# HIVE_SIGHT_WROOM.net
KiCad netlist of a schematic drawn in Altium Designer
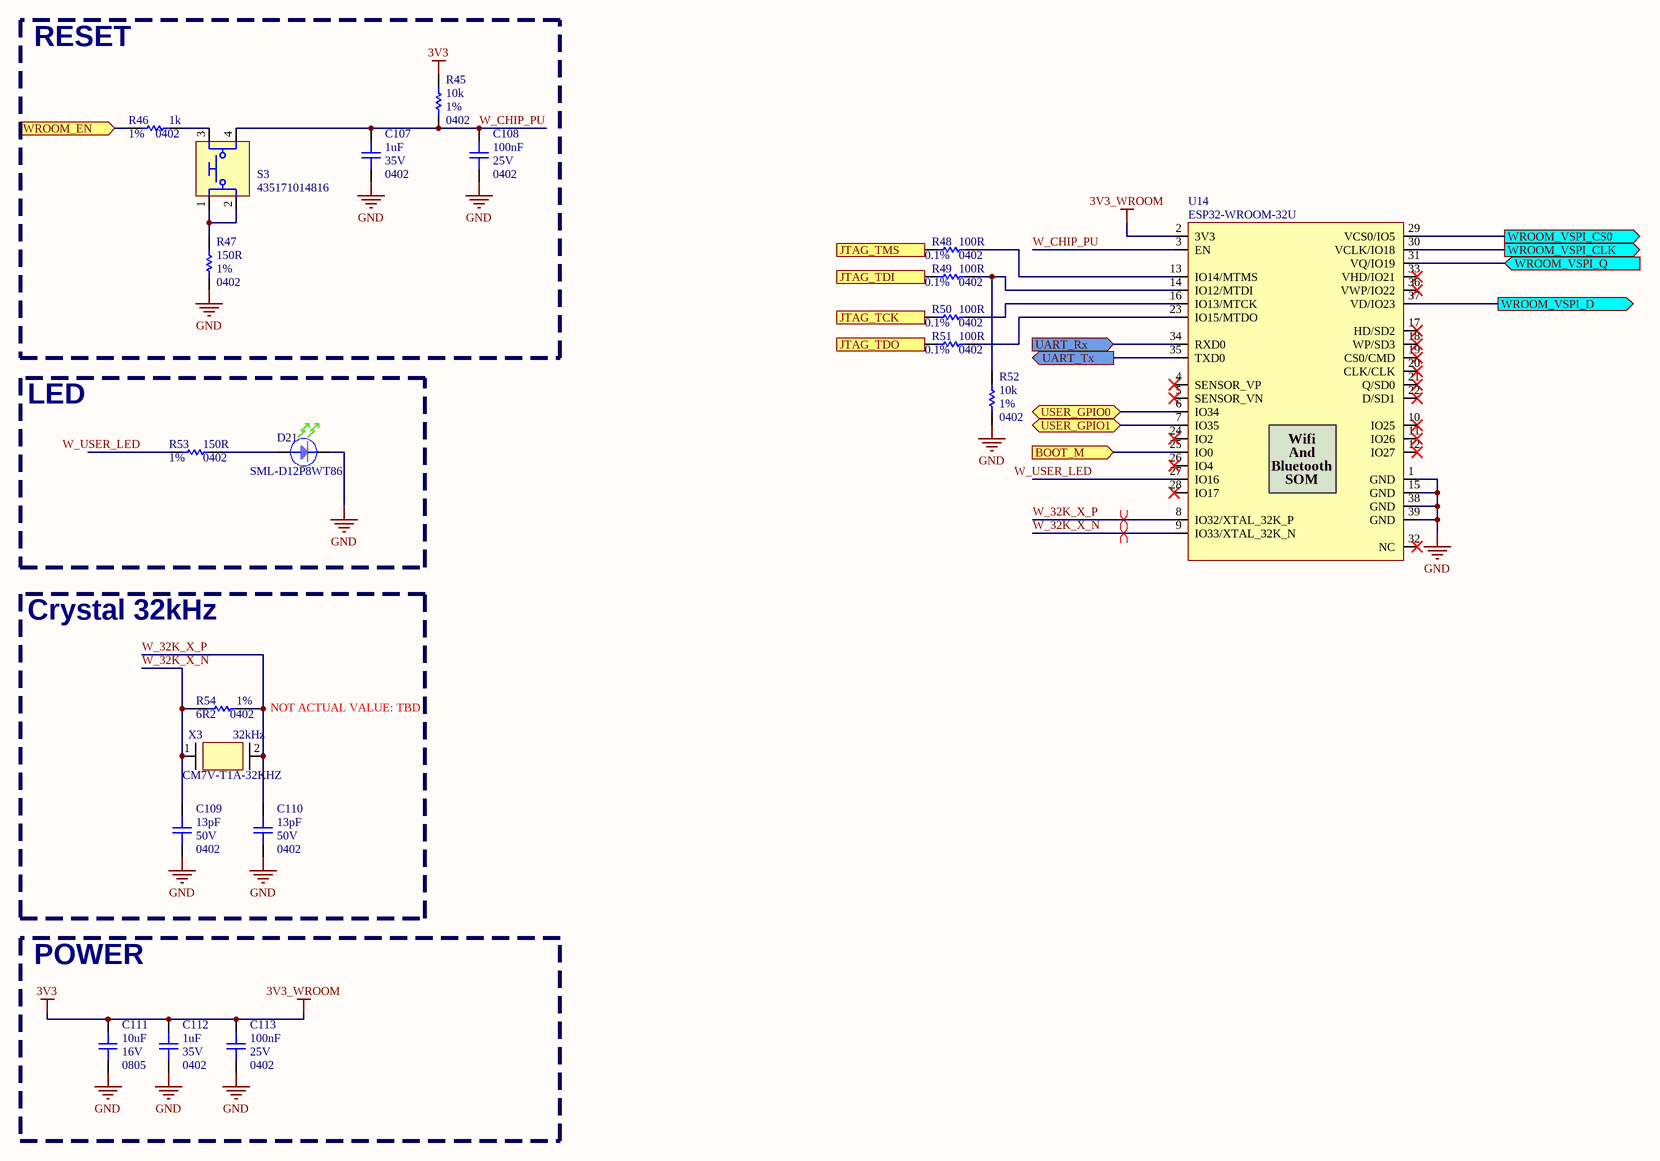
[diagram p0: HIVE_SIGHT_WROOM.SchDoc]

(export (version "E")
  (design (tool "Eeschema 10.0.6"))
  (components
    (comp (ref "C107")
      (value "1uF")
      (footprint "GRAMS_MASTER_LIB_PCB:CAP_CER_0402")
      (description "CAP - CER 1uF 10% 35V X5R - 0402")
      (fields
        (field (name "TOLERANCE") "10%")
        (field (name "PACKAGE") "0402")
        (field (name "VOLTAGE RATING") "35V")
        (field (name "Comment") "CL05A105KL5NRNC")
        (field (name "CREATEDBY/DATE") "Nicolas Roy 2018-10-03")
        (field (name "VERIFIEDBY") "Caroline Paulin - 18 janv 2019")
      )
      (libsource (lib "GRAMS_MASTER_LIB_SCH") (part "CAP_CER_CL05A105KL5NRNC"))
    )
    (comp (ref "C108")
      (value "100nF")
      (footprint "GRAMS_MASTER_LIB_PCB:CAP_CER_0402")
      (description "CAP - CER 0.1µF 10% 25V X7R - 0402")
      (fields
        (field (name "TOLERANCE") "10%")
        (field (name "PACKAGE") "0402")
        (field (name "VOLTAGE RATING") "25V")
        (field (name "Comment") "CGA2B3X7R1E104K050BB")
        (field (name "CREATEDBY/DATE") "Nicolas Roy 2018-11-07")
        (field (name "VERIFIEDBY") "Nicolas V. (2019-01-22)")
      )
      (libsource (lib "GRAMS_MASTER_LIB_SCH") (part "CAP_CER_CGA2B3X7R1E104K050BB"))
    )
    (comp (ref "C109")
      (value "13pF")
      (footprint "CAP_CER_0402")
      (description "CAP - CER 13PF 50V C0G/NP0 - 0402")
      (fields
        (field (name "TOLERANCE") "±5%")
        (field (name "PACKAGE") "0402")
        (field (name "VOLTAGE RATING") "50V")
        (field (name "Comment") "CC0402JRNPO9BN130")
        (field (name "CREATEDBY/DATE") "Hubert Dube - 04/10/20")
        (field (name "VERIFIEDBY") "Louis-Daniel Gaulin - 09/11/2020")
      )
      (libsource (lib "SWARMUS_LIB") (part "CAP_CER_CC0402JRNPO9BN130"))
    )
    (comp (ref "C110")
      (value "13pF")
      (footprint "CAP_CER_0402")
      (description "CAP - CER 13PF 50V C0G/NP0 - 0402")
      (fields
        (field (name "TOLERANCE") "±5%")
        (field (name "PACKAGE") "0402")
        (field (name "VOLTAGE RATING") "50V")
        (field (name "Comment") "CC0402JRNPO9BN130")
        (field (name "CREATEDBY/DATE") "Hubert Dube - 04/10/20")
        (field (name "VERIFIEDBY") "Louis-Daniel Gaulin - 09/11/2020")
      )
      (libsource (lib "SWARMUS_LIB") (part "CAP_CER_CC0402JRNPO9BN130"))
    )
    (comp (ref "C111")
      (value "10uF")
      (footprint "CAP_CER_0805")
      (description "CAP - CER 10UF 10% 16V X5R - 0805")
      (fields
        (field (name "TOLERANCE") "10%")
        (field (name "PACKAGE") "0805")
        (field (name "VOLTAGE RATING") "16V")
        (field (name "Comment") "GRM21BR61C106KE15K")
        (field (name "CREATEDBY/DATE") "Caroline Paulin / 8 août 2018")
        (field (name "VERIFIEDBY") "Nicolas V. (2019-01-22)")
      )
      (libsource (lib "GRAMS_MASTER_LIB") (part "CAP_CER_GRM21BR61C106KE15K"))
    )
    (comp (ref "C112")
      (value "1uF")
      (footprint "GRAMS_MASTER_LIB_PCB:CAP_CER_0402")
      (description "CAP - CER 1uF 10% 35V X5R - 0402")
      (fields
        (field (name "TOLERANCE") "10%")
        (field (name "PACKAGE") "0402")
        (field (name "VOLTAGE RATING") "35V")
        (field (name "Comment") "CL05A105KL5NRNC")
        (field (name "CREATEDBY/DATE") "Nicolas Roy 2018-10-03")
        (field (name "VERIFIEDBY") "Caroline Paulin - 18 janv 2019")
      )
      (libsource (lib "GRAMS_MASTER_LIB_SCH") (part "CAP_CER_CL05A105KL5NRNC"))
    )
    (comp (ref "C113")
      (value "100nF")
      (footprint "GRAMS_MASTER_LIB_PCB:CAP_CER_0402")
      (description "CAP - CER 0.1µF 10% 25V X7R - 0402")
      (fields
        (field (name "TOLERANCE") "10%")
        (field (name "PACKAGE") "0402")
        (field (name "VOLTAGE RATING") "25V")
        (field (name "Comment") "CGA2B3X7R1E104K050BB")
        (field (name "CREATEDBY/DATE") "Nicolas Roy 2018-11-07")
        (field (name "VERIFIEDBY") "Nicolas V. (2019-01-22)")
      )
      (libsource (lib "GRAMS_MASTER_LIB_SCH") (part "CAP_CER_CGA2B3X7R1E104K050BB"))
    )
    (comp (ref "D21")
      (value "SML-D12P8WT86")
      (footprint "GRAMS_MASTER_LIB_PCB:LED_SML-D12P8WT86")
      (description "LED - GREEN DIFFUSED 0603 SMD - 0603")
      (fields
        (field (name "CREATEDBY/DATE") "Keven Deslandes - 2018/11/21")
        (field (name "VERIFIEDBY") "Caroline Paulin - 13 février 2019")
      )
      (libsource (lib "GRAMS_MASTER_LIB_SCH") (part "LED_SML-D12P8WT86"))
    )
    (comp (ref "R45")
      (value "10k")
      (footprint "GRAMS_MASTER_LIB_PCB:RES_0402")
      (description "RES - 10K OHMS 1% 1/16W - 0402")
      (fields
        (field (name "TOLERANCE") "1%")
        (field (name "PACKAGE") "0402")
        (field (name "Comment") "RC0402FR-0710KL")
        (field (name "CREATEDBY/DATE") "Nicolas V. (2018-11-20)")
        (field (name "VERIFIEDBY") "Nicolas V. (2018-11-20)")
      )
      (libsource (lib "GRAMS_MASTER_LIB_SCH") (part "RES_RC0402FR-0710KL"))
    )
    (comp (ref "R46")
      (value "1k")
      (footprint "GRAMS_MASTER_LIB_PCB:RES_0402")
      (description "RES - 1K OHM 1% 1/16W - 0402")
      (fields
        (field (name "TOLERANCE") "1%")
        (field (name "PACKAGE") "0402")
        (field (name "Comment") "RC0402FR-071KL")
        (field (name "CREATEDBY/DATE") "Jonathan Bouchard 2018-07-05")
        (field (name "VERIFIEDBY") "Arnaud Samson 16-07-18")
      )
      (libsource (lib "GRAMS_MASTER_LIB_SCH") (part "RES_RC0402FR-071KL"))
    )
    (comp (ref "R47")
      (value "150R")
      (footprint "RES_0402")
      (description "RES - 150R 1% 1/16W - 0402")
      (fields
        (field (name "TOLERANCE") "1%")
        (field (name "PACKAGE") "0402")
        (field (name "Comment") "RC0402FR-07150RL")
        (field (name "CREATEDBY/DATE") "Jonathan Bouchard 2019-03-25")
        (field (name "VERIFIEDBY") "Nicolas V. (2019-05-02)")
      )
      (libsource (lib "GRAMS_MASTER_LIB") (part "RES_RC0402FR-07150RL"))
    )
    (comp (ref "R48")
      (value "100R")
      (footprint "RES_0402")
      (description "RES - 100 OHM 0.1% 1/20W NON-MAG - 0402")
      (fields
        (field (name "TOLERANCE") "0.1%")
        (field (name "PACKAGE") "0402")
        (field (name "Comment") "PNM0402E1000BST1")
        (field (name "CREATEDBY/DATE") "Jonathan Bouchard 2018-04-3")
        (field (name "VERIFIEDBY") "Arnaud Samson 17-07-18")
      )
      (libsource (lib "GRAMS_MASTER_LIB") (part "RES_NOMAG_PNM0402E1000BST1"))
    )
    (comp (ref "R49")
      (value "100R")
      (footprint "RES_0402")
      (description "RES - 100 OHM 0.1% 1/20W NON-MAG - 0402")
      (fields
        (field (name "TOLERANCE") "0.1%")
        (field (name "PACKAGE") "0402")
        (field (name "Comment") "PNM0402E1000BST1")
        (field (name "CREATEDBY/DATE") "Jonathan Bouchard 2018-04-3")
        (field (name "VERIFIEDBY") "Arnaud Samson 17-07-18")
      )
      (libsource (lib "GRAMS_MASTER_LIB") (part "RES_NOMAG_PNM0402E1000BST1"))
    )
    (comp (ref "R50")
      (value "100R")
      (footprint "RES_0402")
      (description "RES - 100 OHM 0.1% 1/20W NON-MAG - 0402")
      (fields
        (field (name "TOLERANCE") "0.1%")
        (field (name "PACKAGE") "0402")
        (field (name "Comment") "PNM0402E1000BST1")
        (field (name "CREATEDBY/DATE") "Jonathan Bouchard 2018-04-3")
        (field (name "VERIFIEDBY") "Arnaud Samson 17-07-18")
      )
      (libsource (lib "GRAMS_MASTER_LIB") (part "RES_NOMAG_PNM0402E1000BST1"))
    )
    (comp (ref "R51")
      (value "100R")
      (footprint "RES_0402")
      (description "RES - 100 OHM 0.1% 1/20W NON-MAG - 0402")
      (fields
        (field (name "TOLERANCE") "0.1%")
        (field (name "PACKAGE") "0402")
        (field (name "Comment") "PNM0402E1000BST1")
        (field (name "CREATEDBY/DATE") "Jonathan Bouchard 2018-04-3")
        (field (name "VERIFIEDBY") "Arnaud Samson 17-07-18")
      )
      (libsource (lib "GRAMS_MASTER_LIB") (part "RES_NOMAG_PNM0402E1000BST1"))
    )
    (comp (ref "R52")
      (value "10k")
      (footprint "GRAMS_MASTER_LIB_PCB:RES_0402")
      (description "RES - 10K OHMS 1% 1/16W - 0402")
      (fields
        (field (name "TOLERANCE") "1%")
        (field (name "PACKAGE") "0402")
        (field (name "Comment") "RC0402FR-0710KL")
        (field (name "CREATEDBY/DATE") "Nicolas V. (2018-11-20)")
        (field (name "VERIFIEDBY") "Nicolas V. (2018-11-20)")
      )
      (libsource (lib "GRAMS_MASTER_LIB_SCH") (part "RES_RC0402FR-0710KL"))
    )
    (comp (ref "R53")
      (value "150R")
      (footprint "RES_0402")
      (description "RES - 150R 1% 1/16W - 0402")
      (fields
        (field (name "TOLERANCE") "1%")
        (field (name "PACKAGE") "0402")
        (field (name "Comment") "RC0402FR-07150RL")
        (field (name "CREATEDBY/DATE") "Jonathan Bouchard 2019-03-25")
        (field (name "VERIFIEDBY") "Nicolas V. (2019-05-02)")
      )
      (libsource (lib "GRAMS_MASTER_LIB") (part "RES_RC0402FR-07150RL"))
    )
    (comp (ref "R54")
      (value "6R2")
      (footprint "RES_0402")
      (description "RES - 6.2R 1% 1/16W - 0402")
      (fields
        (field (name "TOLERANCE") "1%")
        (field (name "PACKAGE") "0402")
        (field (name "Comment") "RC0402FR-076R2L")
        (field (name "CREATEDBY/DATE") "Hubert Dubé 04/10/2020")
        (field (name "VERIFIEDBY") "Louis-Daniel Gaulin - 09/11/2020")
      )
      (libsource (lib "SWARMUS_LIB") (part "RES_RC0402FR-076R2L"))
    )
    (comp (ref "S3")
      (value "435171014816")
      (footprint "SWI_TACT_435171014816")
      (description "SWI - SWITCH TACTILE SPST-NO 0.05A 12V -SMD")
      (fields
        (field (name "CREATEDBY/DATE") "Hubert Dube - 22/07/20")
        (field (name "VERIFIEDBY") "Louis-Daniel Gaulin / 12-11-2020")
      )
      (libsource (lib "SWARMUS_LIB") (part "SWI_TACT_435171014816"))
    )
    (comp (ref "U14")
      (value "ESP32-WROOM-32U")
      (footprint "COM_ESP32-WROOM-32U(8MB)")
      (description "Bluetooth, WiFi 802.11b/g/n, Bluetooth v4.2  2.4GHz ~ 2.5GHz U.FL Surface Mount")
      (fields
        (field (name "VERIFIEDBY") "Philippe Arsenault - 15/12/2020")
        (field (name "CREATEDBY/DATE") "Hubert Dube -  12/12/20")
      )
      (libsource (lib "SWARMUS_LIB") (part "COM_ESP32-WROOM-32U(8MB)"))
    )
    (comp (ref "X3")
      (value "CM7V-T1A-32KHZ")
      (footprint "CRY_CM7V-T1A-32.768KHZ-12.5PF-20PPM-TA-QC")
      (description "CRY - 32.768KHZ tol:20ppm 12.5PF - 2-SMD")
      (fields
        (field (name "TOLERANCE") "±20ppm")
        (field (name "ALTIUM_VALUE") "32kHz")
        (field (name "CREATEDBY/DATE") "Hubert Dube - 21/07/20")
        (field (name "VERIFIEDBY") "Louis-Daniel Gaulin - 09/11/2020")
      )
      (libsource (lib "SWARMUS_LIB") (part "CRY_CM7V-T1A-32.768KHZ-12.5PF-20PPM-TA-QC"))
    )
  )
  (nets
    (net (code "1") (name "/BOOT_M") (class "Default")
      (node (ref "U14") (pin "25") (pinfunction "IO0_25") (pintype "passive"))
    )
    (net (code "2") (name "/JTAG_TCK") (class "Default")
      (node (ref "R50") (pin "2") (pinfunction "2_2") (pintype "passive"))
    )
    (net (code "3") (name "/JTAG_TDI") (class "Default")
      (node (ref "R49") (pin "2") (pinfunction "2_2") (pintype "passive"))
    )
    (net (code "4") (name "/JTAG_TDO") (class "Default")
      (node (ref "R51") (pin "2") (pinfunction "2_2") (pintype "passive"))
    )
    (net (code "5") (name "/JTAG_TMS") (class "Default")
      (node (ref "R48") (pin "2") (pinfunction "2_2") (pintype "passive"))
    )
    (net (code "6") (name "/UART_Rx") (class "Default")
      (node (ref "U14") (pin "34") (pinfunction "RXD0_34") (pintype "passive"))
    )
    (net (code "7") (name "/UART_Tx") (class "Default")
      (node (ref "U14") (pin "35") (pinfunction "TXD0_35") (pintype "passive"))
    )
    (net (code "8") (name "/USER_GPIO0") (class "Default")
      (node (ref "U14") (pin "6") (pinfunction "IO34_6") (pintype "passive"))
    )
    (net (code "9") (name "/USER_GPIO1") (class "Default")
      (node (ref "U14") (pin "7") (pinfunction "IO35_7") (pintype "passive"))
    )
    (net (code "10") (name "/WROOM_EN") (class "Default")
      (node (ref "R46") (pin "2") (pinfunction "2_2") (pintype "passive"))
    )
    (net (code "11") (name "/WROOM_VSPI_CLK") (class "Default")
      (node (ref "U14") (pin "30") (pinfunction "VCLK/IO18_30") (pintype "passive"))
    )
    (net (code "12") (name "/WROOM_VSPI_CS0") (class "Default")
      (node (ref "U14") (pin "29") (pinfunction "VCS0/IO5_29") (pintype "passive"))
    )
    (net (code "13") (name "/WROOM_VSPI_D") (class "Default")
      (node (ref "U14") (pin "37") (pinfunction "VD/IO23_37") (pintype "passive"))
    )
    (net (code "14") (name "/WROOM_VSPI_Q") (class "Default")
      (node (ref "U14") (pin "31") (pinfunction "VQ/IO19_31") (pintype "passive"))
    )
    (net (code "15") (name "/W_32K_X_N") (class "Default")
      (node (ref "C109") (pin "2") (pinfunction "2_2") (pintype "passive"))
      (node (ref "R54") (pin "2") (pinfunction "2_2") (pintype "passive"))
      (node (ref "U14") (pin "9") (pinfunction "IO33/XTAL_32K_N_9") (pintype "passive"))
      (node (ref "X3") (pin "1") (pinfunction "In/Out_1") (pintype "passive"))
    )
    (net (code "16") (name "/W_32K_X_P") (class "Default")
      (node (ref "C110") (pin "2") (pinfunction "2_2") (pintype "passive"))
      (node (ref "R54") (pin "1") (pinfunction "1_1") (pintype "passive"))
      (node (ref "U14") (pin "8") (pinfunction "IO32/XTAL_32K_P_8") (pintype "passive"))
      (node (ref "X3") (pin "2") (pinfunction "Out/In_2") (pintype "passive"))
    )
    (net (code "17") (name "/W_CHIP_PU") (class "Default")
      (node (ref "C107") (pin "2") (pinfunction "2_2") (pintype "passive"))
      (node (ref "C108") (pin "2") (pinfunction "2_2") (pintype "passive"))
      (node (ref "R45") (pin "1") (pinfunction "1_1") (pintype "passive"))
      (node (ref "S3") (pin "4") (pinfunction "4_4") (pintype "passive"))
      (node (ref "U14") (pin "3") (pinfunction "EN_3") (pintype "passive"))
    )
    (net (code "18") (name "/W_USER_LED") (class "Default")
      (node (ref "R53") (pin "2") (pinfunction "2_2") (pintype "passive"))
      (node (ref "U14") (pin "27") (pinfunction "IO16_27") (pintype "passive"))
    )
    (net (code "19") (name "3V3") (class "Default")
      (node (ref "C111") (pin "2") (pinfunction "2_2") (pintype "passive"))
      (node (ref "C112") (pin "2") (pinfunction "2_2") (pintype "passive"))
      (node (ref "C113") (pin "2") (pinfunction "2_2") (pintype "passive"))
      (node (ref "R45") (pin "2") (pinfunction "2_2") (pintype "passive"))
      (node (ref "U14") (pin "2") (pinfunction "3V3_2") (pintype "passive"))
    )
    (net (code "20") (name "GND") (class "Default")
      (node (ref "C107") (pin "1") (pinfunction "1_1") (pintype "passive"))
      (node (ref "C108") (pin "1") (pinfunction "1_1") (pintype "passive"))
      (node (ref "C109") (pin "1") (pinfunction "1_1") (pintype "passive"))
      (node (ref "C110") (pin "1") (pinfunction "1_1") (pintype "passive"))
      (node (ref "C111") (pin "1") (pinfunction "1_1") (pintype "passive"))
      (node (ref "C112") (pin "1") (pinfunction "1_1") (pintype "passive"))
      (node (ref "C113") (pin "1") (pinfunction "1_1") (pintype "passive"))
      (node (ref "D21") (pin "K") (pinfunction "K_K") (pintype "passive"))
      (node (ref "R47") (pin "1") (pinfunction "1_1") (pintype "passive"))
      (node (ref "R52") (pin "1") (pinfunction "1_1") (pintype "passive"))
      (node (ref "U14") (pin "1") (pinfunction "GND_1") (pintype "passive"))
      (node (ref "U14") (pin "15") (pinfunction "GND_15") (pintype "passive"))
      (node (ref "U14") (pin "38") (pinfunction "GND_38") (pintype "passive"))
      (node (ref "U14") (pin "39") (pinfunction "GND_39") (pintype "passive"))
    )
    (net (code "21") (name "Net-(D21-PadA)") (class "Default")
      (node (ref "D21") (pin "A") (pinfunction "A_A") (pintype "passive"))
      (node (ref "R53") (pin "1") (pinfunction "1_1") (pintype "passive"))
    )
    (net (code "22") (name "Net-(R46-Pad1)") (class "Default")
      (node (ref "R46") (pin "1") (pinfunction "1_1") (pintype "passive"))
      (node (ref "S3") (pin "3") (pinfunction "3_3") (pintype "passive"))
    )
    (net (code "23") (name "Net-(R47-Pad2)") (class "Default")
      (node (ref "R47") (pin "2") (pinfunction "2_2") (pintype "passive"))
      (node (ref "S3") (pin "1") (pinfunction "1_1") (pintype "passive"))
      (node (ref "S3") (pin "2") (pinfunction "2_2") (pintype "passive"))
    )
    (net (code "24") (name "Net-(U14-IO12{slash}MTDI)") (class "Default")
      (node (ref "R49") (pin "1") (pinfunction "1_1") (pintype "passive"))
      (node (ref "R52") (pin "2") (pinfunction "2_2") (pintype "passive"))
      (node (ref "U14") (pin "14") (pinfunction "IO12/MTDI_14") (pintype "passive"))
    )
    (net (code "25") (name "Net-(U14-IO13{slash}MTCK)") (class "Default")
      (node (ref "R50") (pin "1") (pinfunction "1_1") (pintype "passive"))
      (node (ref "U14") (pin "16") (pinfunction "IO13/MTCK_16") (pintype "passive"))
    )
    (net (code "26") (name "Net-(U14-IO14{slash}MTMS)") (class "Default")
      (node (ref "R48") (pin "1") (pinfunction "1_1") (pintype "passive"))
      (node (ref "U14") (pin "13") (pinfunction "IO14/MTMS_13") (pintype "passive"))
    )
    (net (code "27") (name "Net-(U14-IO15{slash}MTDO)") (class "Default")
      (node (ref "R51") (pin "1") (pinfunction "1_1") (pintype "passive"))
      (node (ref "U14") (pin "23") (pinfunction "IO15/MTDO_23") (pintype "passive"))
    )
    (net (code "28") (name "unconnected-(U14-CLK{slash}CLK-Pad20)") (class "Default")
      (node (ref "U14") (pin "20") (pinfunction "CLK/CLK_20") (pintype "passive+no_connect"))
    )
    (net (code "29") (name "unconnected-(U14-CS0{slash}CMD-Pad19)") (class "Default")
      (node (ref "U14") (pin "19") (pinfunction "CS0/CMD_19") (pintype "passive+no_connect"))
    )
    (net (code "30") (name "unconnected-(U14-D{slash}SD1-Pad22)") (class "Default")
      (node (ref "U14") (pin "22") (pinfunction "D/SD1_22") (pintype "passive+no_connect"))
    )
    (net (code "31") (name "unconnected-(U14-HD{slash}SD2-Pad17)") (class "Default")
      (node (ref "U14") (pin "17") (pinfunction "HD/SD2_17") (pintype "passive+no_connect"))
    )
    (net (code "32") (name "unconnected-(U14-IO2-Pad24)") (class "Default")
      (node (ref "U14") (pin "24") (pinfunction "IO2_24") (pintype "passive+no_connect"))
    )
    (net (code "33") (name "unconnected-(U14-IO4-Pad26)") (class "Default")
      (node (ref "U14") (pin "26") (pinfunction "IO4_26") (pintype "passive+no_connect"))
    )
    (net (code "34") (name "unconnected-(U14-IO17-Pad28)") (class "Default")
      (node (ref "U14") (pin "28") (pinfunction "IO17_28") (pintype "passive+no_connect"))
    )
    (net (code "35") (name "unconnected-(U14-IO25-Pad10)") (class "Default")
      (node (ref "U14") (pin "10") (pinfunction "IO25_10") (pintype "passive+no_connect"))
    )
    (net (code "36") (name "unconnected-(U14-IO26-Pad11)") (class "Default")
      (node (ref "U14") (pin "11") (pinfunction "IO26_11") (pintype "passive+no_connect"))
    )
    (net (code "37") (name "unconnected-(U14-IO27-Pad12)") (class "Default")
      (node (ref "U14") (pin "12") (pinfunction "IO27_12") (pintype "passive+no_connect"))
    )
    (net (code "38") (name "unconnected-(U14-NC-Pad32)") (class "Default")
      (node (ref "U14") (pin "32") (pinfunction "NC_32") (pintype "passive+no_connect"))
    )
    (net (code "39") (name "unconnected-(U14-Q{slash}SD0-Pad21)") (class "Default")
      (node (ref "U14") (pin "21") (pinfunction "Q/SD0_21") (pintype "passive+no_connect"))
    )
    (net (code "40") (name "unconnected-(U14-SENSOR_VN-Pad5)") (class "Default")
      (node (ref "U14") (pin "5") (pinfunction "SENSOR_VN_5") (pintype "passive+no_connect"))
    )
    (net (code "41") (name "unconnected-(U14-SENSOR_VP-Pad4)") (class "Default")
      (node (ref "U14") (pin "4") (pinfunction "SENSOR_VP_4") (pintype "passive+no_connect"))
    )
    (net (code "42") (name "unconnected-(U14-VHD{slash}IO21-Pad33)") (class "Default")
      (node (ref "U14") (pin "33") (pinfunction "VHD/IO21_33") (pintype "passive+no_connect"))
    )
    (net (code "43") (name "unconnected-(U14-VWP{slash}IO22-Pad36)") (class "Default")
      (node (ref "U14") (pin "36") (pinfunction "VWP/IO22_36") (pintype "passive+no_connect"))
    )
    (net (code "44") (name "unconnected-(U14-WP{slash}SD3-Pad18)") (class "Default")
      (node (ref "U14") (pin "18") (pinfunction "WP/SD3_18") (pintype "passive+no_connect"))
    )
  )
)
